# the-bicho.net
KiCad netlist of a schematic drawn in Altium Designer
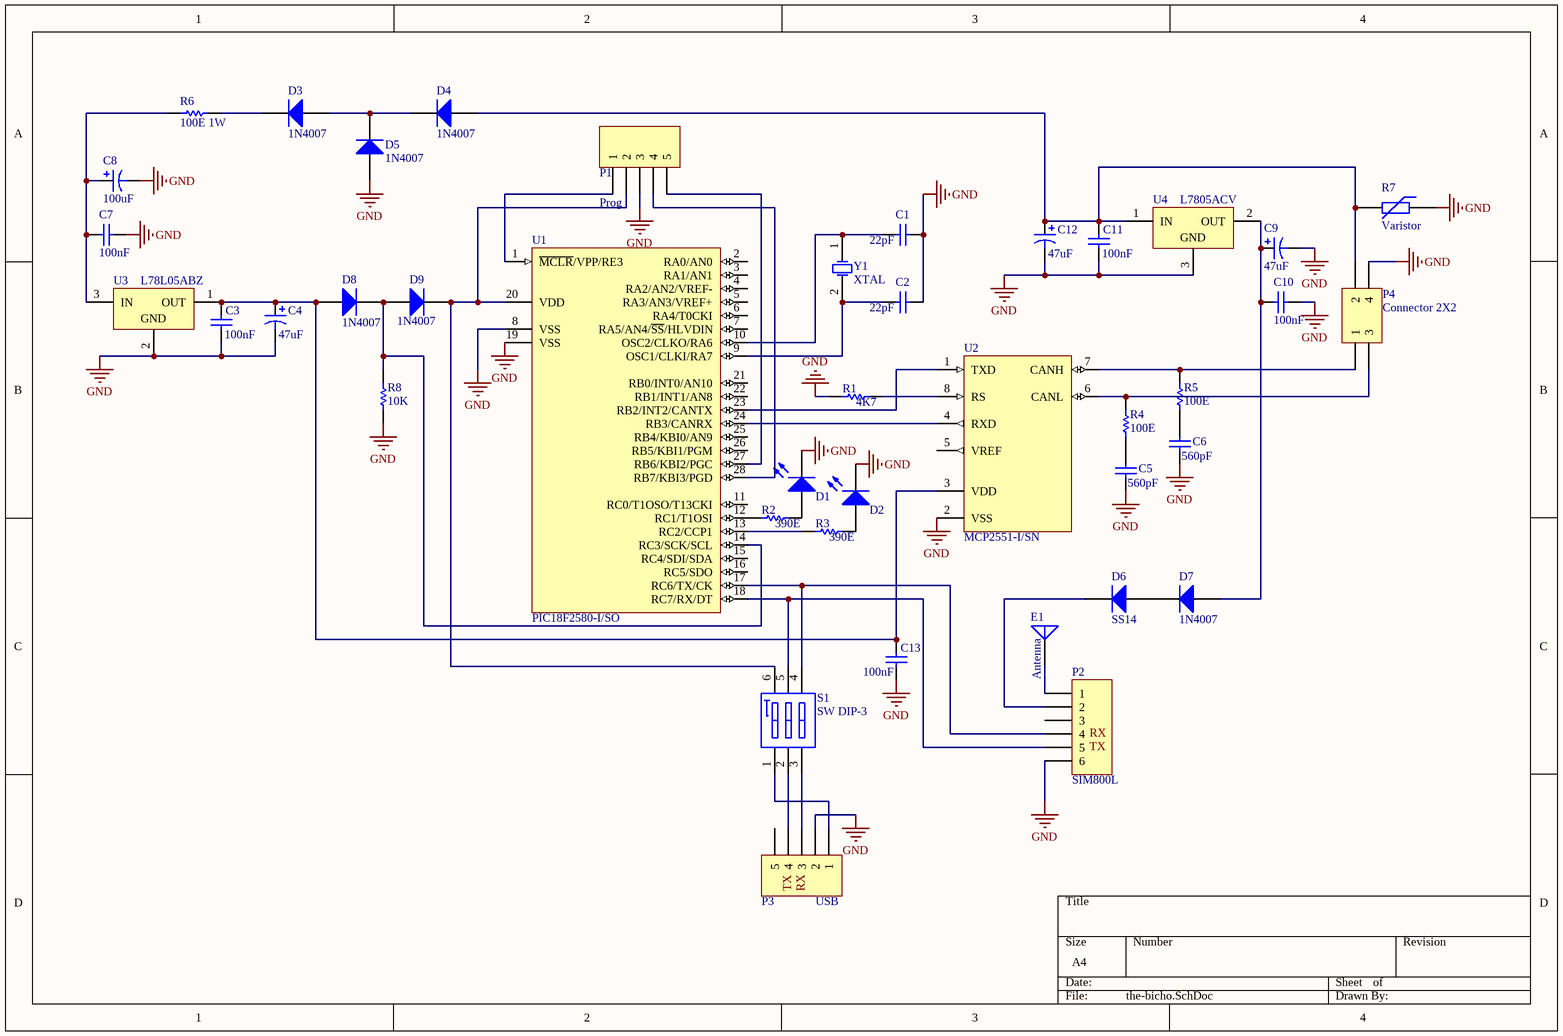
[diagram p0: the-bicho.SchDoc]

(export (version "E")
  (design (tool "Eeschema 10.0.6"))
  (components
    (comp (ref "C1")
      (value "22pF")
      (footprint "C0805:PCBComponent_1")
      (description "Capacitor")
      (fields (field (name "PUBLISHER") "Altium Limited"))
      (libsource (lib "Miscellaneous Devices") (part "Cap"))
    )
    (comp (ref "C2")
      (value "22pF")
      (footprint "C0805:PCBComponent_1")
      (description "Capacitor")
      (fields (field (name "PUBLISHER") "Altium Limited"))
      (libsource (lib "Miscellaneous Devices") (part "Cap"))
    )
    (comp (ref "C3")
      (value "100nF")
      (footprint "C0805:PCBComponent_1")
      (description "Capacitor")
      (fields (field (name "PUBLISHER") "Altium Limited"))
      (libsource (lib "Miscellaneous Devices") (part "Cap"))
    )
    (comp (ref "C4")
      (value "47uF")
      (footprint "C-electro:PCBComponent_1")
      (description "Polarized Capacitor (Radial)")
      (fields (field (name "PUBLISHER") "Altium Limited"))
      (libsource (lib "Miscellaneous Devices") (part "Cap Pol1"))
    )
    (comp (ref "C5")
      (value "560pF")
      (footprint "C0805:PCBComponent_1")
      (description "Capacitor")
      (fields (field (name "PUBLISHER") "Altium Limited"))
      (libsource (lib "Miscellaneous Devices") (part "Cap"))
    )
    (comp (ref "C6")
      (value "560pF")
      (footprint "C0805:PCBComponent_1")
      (description "Capacitor")
      (fields (field (name "PUBLISHER") "Altium Limited"))
      (libsource (lib "Miscellaneous Devices") (part "Cap"))
    )
    (comp (ref "C7")
      (value "100nF")
      (footprint "C0805:PCBComponent_1")
      (description "Capacitor")
      (fields (field (name "PUBLISHER") "Altium Limited"))
      (libsource (lib "Miscellaneous Devices") (part "Cap"))
    )
    (comp (ref "C8")
      (value "100uF")
      (footprint "C-electro:PCBComponent_1")
      (description "Polarized Capacitor (Radial)")
      (fields (field (name "PUBLISHER") "Altium Limited"))
      (libsource (lib "Miscellaneous Devices") (part "Cap Pol1"))
    )
    (comp (ref "C9")
      (value "47uF")
      (footprint "C-electro:PCBComponent_1")
      (description "Polarized Capacitor (Radial)")
      (fields (field (name "PUBLISHER") "Altium Limited"))
      (libsource (lib "Miscellaneous Devices") (part "Cap Pol1"))
    )
    (comp (ref "C10")
      (value "100nF")
      (footprint "C0805:PCBComponent_1")
      (description "Capacitor")
      (fields (field (name "PUBLISHER") "Altium Limited"))
      (libsource (lib "Miscellaneous Devices") (part "Cap"))
    )
    (comp (ref "C11")
      (value "100nF")
      (footprint "C0805:PCBComponent_1")
      (description "Capacitor")
      (fields (field (name "PUBLISHER") "Altium Limited"))
      (libsource (lib "Miscellaneous Devices") (part "Cap"))
    )
    (comp (ref "C12")
      (value "47uF")
      (footprint "C-electro:PCBComponent_1")
      (description "Polarized Capacitor (Radial)")
      (fields (field (name "PUBLISHER") "Altium Limited"))
      (libsource (lib "Miscellaneous Devices") (part "Cap Pol1"))
    )
    (comp (ref "C13")
      (value "100nF")
      (footprint "C0805:PCBComponent_1")
      (description "Capacitor")
      (fields (field (name "PUBLISHER") "Altium Limited"))
      (libsource (lib "Miscellaneous Devices") (part "Cap"))
    )
    (comp (ref "D1")
      (value "~")
      (footprint "Led smd 90:PCBComponent_1")
      (description "Typical INFRARED GaAs LED")
      (fields (field (name "PUBLISHER") "Altium Limited"))
      (libsource (lib "Miscellaneous Devices") (part "LED0"))
    )
    (comp (ref "D2")
      (value "~")
      (footprint "Led smd 90:PCBComponent_1")
      (description "Typical INFRARED GaAs LED")
      (fields (field (name "PUBLISHER") "Altium Limited"))
      (libsource (lib "Miscellaneous Devices") (part "LED0"))
    )
    (comp (ref "D3")
      (value "1N4007")
      (footprint "Diodo SMD:PCBComponent_1")
      (description "1 Amp General Purpose Rectifier")
      (fields (field (name "PUBLISHER") "Altium Limited"))
      (libsource (lib "Miscellaneous Devices") (part "Diode 1N4007"))
    )
    (comp (ref "D4")
      (value "1N4007")
      (footprint "Diodo SMD:PCBComponent_1")
      (description "1 Amp General Purpose Rectifier")
      (fields (field (name "PUBLISHER") "Altium Limited"))
      (libsource (lib "Miscellaneous Devices") (part "Diode 1N4007"))
    )
    (comp (ref "D5")
      (value "1N4007")
      (footprint "Diodo SMD:PCBComponent_1")
      (description "1 Amp General Purpose Rectifier")
      (fields (field (name "PUBLISHER") "Altium Limited"))
      (libsource (lib "Miscellaneous Devices") (part "Diode 1N4007"))
    )
    (comp (ref "D6")
      (value "SS14")
      (footprint "Diodo SMD:PCBComponent_1")
      (description "1 Amp General Purpose Rectifier")
      (fields (field (name "PUBLISHER") "Altium Limited"))
      (libsource (lib "Miscellaneous Devices") (part "Diode 1N4007"))
    )
    (comp (ref "D7")
      (value "1N4007")
      (footprint "Diodo SMD:PCBComponent_1")
      (description "1 Amp General Purpose Rectifier")
      (fields (field (name "PUBLISHER") "Altium Limited"))
      (libsource (lib "Miscellaneous Devices") (part "Diode 1N4007"))
    )
    (comp (ref "D8")
      (value "1N4007")
      (footprint "Diodo SMD:PCBComponent_1")
      (description "1 Amp General Purpose Rectifier")
      (fields (field (name "PUBLISHER") "Altium Limited"))
      (libsource (lib "Miscellaneous Devices") (part "Diode 1N4007"))
    )
    (comp (ref "D9")
      (value "1N4007")
      (footprint "Diodo SMD:PCBComponent_1")
      (description "1 Amp General Purpose Rectifier")
      (fields (field (name "PUBLISHER") "Altium Limited"))
      (libsource (lib "Miscellaneous Devices") (part "Diode 1N4007"))
    )
    (comp (ref "E1")
      (value "Antenna")
      (footprint "PIN1")
      (description "Generic Antenna")
      (fields (field (name "PUBLISHER") "Altium Limited"))
      (libsource (lib "Miscellaneous Devices") (part "Antenna"))
    )
    (comp (ref "P1")
      (value "Prog")
      (footprint "HDR1X5")
      (description "Header, 5-Pin")
      (fields (field (name "PUBLISHER") "Altium Limited"))
      (libsource (lib "Miscellaneous Connectors") (part "Header 5"))
    )
    (comp (ref "P2")
      (value "SIM800L")
      (footprint "HDR1X6")
      (description "Header, 6-Pin")
      (fields (field (name "PUBLISHER") "Altium Limited"))
      (libsource (lib "Miscellaneous Connectors") (part "Header 6"))
    )
    (comp (ref "P3")
      (value "USB")
      (footprint "HDR1X5")
      (description "Header, 5-Pin")
      (fields (field (name "PUBLISHER") "Altium Limited"))
      (libsource (lib "") (part "Header 5_1"))
    )
    (comp (ref "P4")
      (value "Connector 2X2")
      (footprint "Conec 2x2:PCBComponent_1")
      (description "Header, 2-Pin, Dual row")
      (fields (field (name "PUBLISHER") "Altium Limited"))
      (libsource (lib "Miscellaneous Connectors") (part "Header 2X2"))
    )
    (comp (ref "R1")
      (value "4K7")
      (footprint "R0805:PCBComponent_1")
      (description "Resistor")
      (fields (field (name "PUBLISHER") "Altium Limited"))
      (libsource (lib "Miscellaneous Devices") (part "Res1"))
    )
    (comp (ref "R2")
      (value "390E")
      (footprint "R0805:PCBComponent_1")
      (description "Resistor")
      (fields (field (name "PUBLISHER") "Altium Limited"))
      (libsource (lib "Miscellaneous Devices") (part "Res1"))
    )
    (comp (ref "R3")
      (value "390E")
      (footprint "R0805:PCBComponent_1")
      (description "Resistor")
      (fields (field (name "PUBLISHER") "Altium Limited"))
      (libsource (lib "Miscellaneous Devices") (part "Res1"))
    )
    (comp (ref "R4")
      (value "100E")
      (footprint "R0805:PCBComponent_1")
      (description "Resistor")
      (fields (field (name "PUBLISHER") "Altium Limited"))
      (libsource (lib "Miscellaneous Devices") (part "Res1"))
    )
    (comp (ref "R5")
      (value "100E")
      (footprint "R0805:PCBComponent_1")
      (description "Resistor")
      (fields (field (name "PUBLISHER") "Altium Limited"))
      (libsource (lib "Miscellaneous Devices") (part "Res1"))
    )
    (comp (ref "R6")
      (value "100E 1W")
      (footprint "R1watt:PCBComponent_1")
      (description "Resistor")
      (fields (field (name "PUBLISHER") "Altium Limited"))
      (libsource (lib "Miscellaneous Devices") (part "Res1"))
    )
    (comp (ref "R7")
      (value "Varistor")
      (footprint "Vr-07:PCBComponent_1")
      (description "Varistor (Voltage-Sensitive Resistor)")
      (fields (field (name "PUBLISHER") "Altium Limited"))
      (libsource (lib "Miscellaneous Devices") (part "Res Varistor"))
    )
    (comp (ref "R8")
      (value "10K")
      (footprint "R0805:PCBComponent_1")
      (description "Resistor")
      (fields (field (name "PUBLISHER") "Altium Limited"))
      (libsource (lib "Miscellaneous Devices") (part "Res1"))
    )
    (comp (ref "S1")
      (value "SW DIP-3")
      (footprint "Dip 3 piano:PCBComponent_1")
      (description "DIP Switch, 3 Position, SPST")
      (fields (field (name "PUBLISHER") "Altium Limited"))
      (libsource (lib "Miscellaneous Devices") (part "SW DIP-3"))
    )
    (comp (ref "U1")
      (value "PIC18F2580-I/SO")
      (footprint "SOIC-SO28_N")
      (fields (field (name "PUBLISHER") "Altium Limited"))
      (libsource (lib "Microchip Microcontroller 8-Bit PIC18") (part "PIC18F2580-I/SO"))
    )
    (comp (ref "U2")
      (value "MCP2551-I/SN")
      (footprint "SOIC-SN8_N")
      (description "High-Speed CAN Transceiver, 8-Pin SOIC, Industrial Temperature")
      (fields (field (name "PUBLISHER") "Altium Limited"))
      (libsource (lib "Microchip Interface") (part "MCP2551-I/SN"))
    )
    (comp (ref "U3")
      (value "L78L05ABZ")
      (footprint "78Lxx:PCBComponent_1")
      (description "Positive Voltage Regulator")
      (fields (field (name "PUBLISHER") "Altium Limited"))
      (libsource (lib "ST Power Mgt Voltage Regulator") (part "L78L05ABZ"))
    )
    (comp (ref "U4")
      (value "L7805ACV")
      (footprint "TO220ABN")
      (description "Precision 1A Regulator")
      (fields (field (name "PUBLISHER") "Altium Limited"))
      (libsource (lib "ST Power Mgt Voltage Regulator") (part "L7805ACV"))
    )
    (comp (ref "Y1")
      (value "XTAL")
      (footprint "cristal:PCBComponent_1")
      (description "Crystal Oscillator")
      (fields (field (name "PUBLISHER") "Altium Limited"))
      (libsource (lib "Miscellaneous Devices") (part "XTAL"))
    )
  )
  (nets
    (net (code "3") (name "GND") (class "Default")
      (node (ref "C1") (pin "2") (pinfunction "2_2") (pintype "passive"))
      (node (ref "C10") (pin "1") (pinfunction "1_1") (pintype "passive"))
      (node (ref "C11") (pin "1") (pinfunction "1_1") (pintype "passive"))
      (node (ref "C12") (pin "2") (pinfunction "2_2") (pintype "passive"))
      (node (ref "C13") (pin "1") (pinfunction "1_1") (pintype "passive"))
      (node (ref "C2") (pin "2") (pinfunction "2_2") (pintype "passive"))
      (node (ref "C3") (pin "1") (pinfunction "1_1") (pintype "passive"))
      (node (ref "C4") (pin "2") (pinfunction "2_2") (pintype "passive"))
      (node (ref "C5") (pin "1") (pinfunction "1_1") (pintype "passive"))
      (node (ref "C6") (pin "1") (pinfunction "1_1") (pintype "passive"))
      (node (ref "C7") (pin "1") (pinfunction "1_1") (pintype "passive"))
      (node (ref "C8") (pin "2") (pinfunction "2_2") (pintype "passive"))
      (node (ref "C9") (pin "2") (pinfunction "2_2") (pintype "passive"))
      (node (ref "D1") (pin "2") (pinfunction "K_2") (pintype "passive"))
      (node (ref "D2") (pin "2") (pinfunction "K_2") (pintype "passive"))
      (node (ref "D5") (pin "1") (pinfunction "A_1") (pintype "passive"))
      (node (ref "P1") (pin "3") (pinfunction "3_3") (pintype "passive"))
      (node (ref "P2") (pin "6") (pinfunction "6_6") (pintype "passive"))
      (node (ref "P3") (pin "2") (pinfunction "2_2") (pintype "passive"))
      (node (ref "P4") (pin "4") (pinfunction "4_4") (pintype "passive"))
      (node (ref "R1") (pin "1") (pinfunction "1_1") (pintype "passive"))
      (node (ref "R7") (pin "1") (pinfunction "1_1") (pintype "passive"))
      (node (ref "R8") (pin "1") (pinfunction "1_1") (pintype "passive"))
      (node (ref "U1") (pin "19") (pinfunction "VSS_19") (pintype "power_in"))
      (node (ref "U1") (pin "8") (pinfunction "VSS_8") (pintype "power_in"))
      (node (ref "U2") (pin "2") (pinfunction "VSS_2") (pintype "power_in"))
      (node (ref "U3") (pin "2") (pinfunction "GND_2") (pintype "power_in"))
      (node (ref "U4") (pin "3") (pinfunction "GND_3") (pintype "power_in"))
    )
    (net (code "4") (name "Net-(C5-Pad2)") (class "Default")
      (node (ref "C5") (pin "2") (pinfunction "2_2") (pintype "passive"))
      (node (ref "R4") (pin "1") (pinfunction "1_1") (pintype "passive"))
    )
    (net (code "5") (name "Net-(C6-Pad2)") (class "Default")
      (node (ref "C6") (pin "2") (pinfunction "2_2") (pintype "passive"))
      (node (ref "R5") (pin "1") (pinfunction "1_1") (pintype "passive"))
    )
    (net (code "6") (name "Net-(D1-A)") (class "Default")
      (node (ref "D1") (pin "1") (pinfunction "A_1") (pintype "passive"))
      (node (ref "R2") (pin "2") (pinfunction "2_2") (pintype "passive"))
    )
    (net (code "7") (name "Net-(D2-A)") (class "Default")
      (node (ref "D2") (pin "1") (pinfunction "A_1") (pintype "passive"))
      (node (ref "R3") (pin "2") (pinfunction "2_2") (pintype "passive"))
    )
    (net (code "8") (name "Net-(D3-A)") (class "Default")
      (node (ref "D3") (pin "1") (pinfunction "A_1") (pintype "passive"))
      (node (ref "D4") (pin "2") (pinfunction "K_2") (pintype "passive"))
      (node (ref "D5") (pin "2") (pinfunction "K_2") (pintype "passive"))
    )
    (net (code "9") (name "Net-(D3-K)") (class "Default")
      (node (ref "D3") (pin "2") (pinfunction "K_2") (pintype "passive"))
      (node (ref "R6") (pin "1") (pinfunction "1_1") (pintype "passive"))
    )
    (net (code "10") (name "Net-(D4-A)") (class "Default")
      (node (ref "C11") (pin "2") (pinfunction "2_2") (pintype "passive"))
      (node (ref "C12") (pin "1") (pinfunction "1_1") (pintype "passive"))
      (node (ref "D4") (pin "1") (pinfunction "A_1") (pintype "passive"))
      (node (ref "P4") (pin "2") (pinfunction "2_2") (pintype "passive"))
      (node (ref "R7") (pin "2") (pinfunction "2_2") (pintype "passive"))
      (node (ref "U4") (pin "1") (pinfunction "IN_1") (pintype "power_in"))
    )
    (net (code "11") (name "Net-(D6-A)") (class "Default")
      (node (ref "D6") (pin "1") (pinfunction "A_1") (pintype "passive"))
      (node (ref "D7") (pin "2") (pinfunction "K_2") (pintype "passive"))
    )
    (net (code "12") (name "Net-(D6-K)") (class "Default")
      (node (ref "D6") (pin "2") (pinfunction "K_2") (pintype "passive"))
      (node (ref "P2") (pin "2") (pinfunction "2_2") (pintype "passive"))
    )
    (net (code "13") (name "Net-(D7-A)") (class "Default")
      (node (ref "C10") (pin "2") (pinfunction "2_2") (pintype "passive"))
      (node (ref "C9") (pin "1") (pinfunction "1_1") (pintype "passive"))
      (node (ref "D7") (pin "1") (pinfunction "A_1") (pintype "passive"))
      (node (ref "U4") (pin "2") (pinfunction "OUT_2") (pintype "power_in"))
    )
    (net (code "14") (name "Net-(D8-A)") (class "Default")
      (node (ref "C13") (pin "2") (pinfunction "2_2") (pintype "passive"))
      (node (ref "C3") (pin "2") (pinfunction "2_2") (pintype "passive"))
      (node (ref "C4") (pin "1") (pinfunction "1_1") (pintype "passive"))
      (node (ref "D8") (pin "1") (pinfunction "A_1") (pintype "passive"))
      (node (ref "U2") (pin "3") (pinfunction "VDD_3") (pintype "power_in"))
      (node (ref "U3") (pin "1") (pinfunction "OUT_1") (pintype "power_in"))
    )
    (net (code "15") (name "Net-(D8-K)") (class "Default")
      (node (ref "D8") (pin "2") (pinfunction "K_2") (pintype "passive"))
      (node (ref "D9") (pin "1") (pinfunction "A_1") (pintype "passive"))
      (node (ref "R8") (pin "2") (pinfunction "2_2") (pintype "passive"))
      (node (ref "U1") (pin "14") (pinfunction "RC3/SCK/SCL_14") (pintype "bidirectional"))
    )
    (net (code "16") (name "Net-(D9-K)") (class "Default")
      (node (ref "D9") (pin "2") (pinfunction "K_2") (pintype "passive"))
      (node (ref "P1") (pin "2") (pinfunction "2_2") (pintype "passive"))
      (node (ref "S1") (pin "6") (pinfunction "B1_6") (pintype "passive"))
      (node (ref "U1") (pin "20") (pinfunction "VDD_20") (pintype "power_in"))
    )
    (net (code "17") (name "Net-(E1-A)") (class "Default")
      (node (ref "E1") (pin "1") (pinfunction "A_1") (pintype "passive"))
      (node (ref "P2") (pin "1") (pinfunction "1_1") (pintype "passive"))
    )
    (net (code "18") (name "Net-(S1-A1)") (class "Default")
      (node (ref "P3") (pin "1") (pinfunction "1_1") (pintype "passive"))
      (node (ref "S1") (pin "1") (pinfunction "A1_1") (pintype "passive"))
    )
    (net (code "19") (name "Net-(S1-A2)") (class "Default")
      (node (ref "P3") (pin "4") (pinfunction "4_4") (pintype "passive"))
      (node (ref "S1") (pin "2") (pinfunction "A2_2") (pintype "passive"))
    )
    (net (code "20") (name "Net-(S1-A3)") (class "Default")
      (node (ref "P3") (pin "3") (pinfunction "3_3") (pintype "passive"))
      (node (ref "S1") (pin "3") (pinfunction "A3_3") (pintype "passive"))
    )
    (net (code "21") (name "Net-(S1-B2)") (class "Default")
      (node (ref "P2") (pin "5") (pinfunction "5_5") (pintype "passive"))
      (node (ref "S1") (pin "5") (pinfunction "B2_5") (pintype "passive"))
      (node (ref "U1") (pin "18") (pinfunction "RC7/RX/DT_18") (pintype "bidirectional"))
    )
    (net (code "22") (name "Net-(S1-B3)") (class "Default")
      (node (ref "P2") (pin "4") (pinfunction "4_4") (pintype "passive"))
      (node (ref "S1") (pin "4") (pinfunction "B3_4") (pintype "passive"))
      (node (ref "U1") (pin "17") (pinfunction "RC6/TX/CK_17") (pintype "bidirectional"))
    )
    (net (code "23") (name "Net-(U1-OSC1{slash}CLKI{slash}RA7)") (class "Default")
      (node (ref "C2") (pin "1") (pinfunction "1_1") (pintype "passive"))
      (node (ref "U1") (pin "9") (pinfunction "OSC1/CLKI/RA7_9") (pintype "bidirectional"))
      (node (ref "Y1") (pin "2") (pinfunction "OSC2_2") (pintype "passive"))
    )
    (net (code "24") (name "Net-(U1-OSC2{slash}CLKO{slash}RA6)") (class "Default")
      (node (ref "C1") (pin "1") (pinfunction "1_1") (pintype "passive"))
      (node (ref "U1") (pin "10") (pinfunction "OSC2/CLKO/RA6_10") (pintype "bidirectional"))
      (node (ref "Y1") (pin "1") (pinfunction "OSC1_1") (pintype "passive"))
    )
    (net (code "25") (name "Net-(U1-RB2{slash}INT2{slash}CANTX)") (class "Default")
      (node (ref "U1") (pin "23") (pinfunction "RB2/INT2/CANTX_23") (pintype "bidirectional"))
      (node (ref "U2") (pin "1") (pinfunction "TXD_1") (pintype "input"))
    )
    (net (code "26") (name "Net-(U1-RB3{slash}CANRX)") (class "Default")
      (node (ref "U1") (pin "24") (pinfunction "RB3/CANRX_24") (pintype "bidirectional"))
      (node (ref "U2") (pin "4") (pinfunction "RXD_4") (pintype "output"))
    )
    (net (code "27") (name "Net-(U1-RB6{slash}KBI2{slash}PGC)") (class "Default")
      (node (ref "P1") (pin "5") (pinfunction "5_5") (pintype "passive"))
      (node (ref "U1") (pin "27") (pinfunction "RB6/KBI2/PGC_27") (pintype "bidirectional"))
    )
    (net (code "28") (name "Net-(U1-RB7{slash}KBI3{slash}PGD)") (class "Default")
      (node (ref "P1") (pin "4") (pinfunction "4_4") (pintype "passive"))
      (node (ref "U1") (pin "28") (pinfunction "RB7/KBI3/PGD_28") (pintype "bidirectional"))
    )
    (net (code "29") (name "Net-(U1-RC1{slash}T1OSI)") (class "Default")
      (node (ref "R2") (pin "1") (pinfunction "1_1") (pintype "passive"))
      (node (ref "U1") (pin "12") (pinfunction "RC1/T1OSI_12") (pintype "bidirectional"))
    )
    (net (code "30") (name "Net-(U1-RC2{slash}CCP1)") (class "Default")
      (node (ref "R3") (pin "1") (pinfunction "1_1") (pintype "passive"))
      (node (ref "U1") (pin "13") (pinfunction "RC2/CCP1_13") (pintype "bidirectional"))
    )
    (net (code "31") (name "Net-(U1-~{MCLR}{slash}VPP{slash}RE3)") (class "Default")
      (node (ref "P1") (pin "1") (pinfunction "1_1") (pintype "passive"))
      (node (ref "U1") (pin "1") (pinfunction "~{MCLR}/VPP/RE3_1") (pintype "input"))
    )
    (net (code "32") (name "Net-(U2-CANH)") (class "Default")
      (node (ref "P4") (pin "1") (pinfunction "1_1") (pintype "passive"))
      (node (ref "R5") (pin "2") (pinfunction "2_2") (pintype "passive"))
      (node (ref "U2") (pin "7") (pinfunction "CANH_7") (pintype "bidirectional"))
    )
    (net (code "33") (name "Net-(U2-CANL)") (class "Default")
      (node (ref "P4") (pin "3") (pinfunction "3_3") (pintype "passive"))
      (node (ref "R4") (pin "2") (pinfunction "2_2") (pintype "passive"))
      (node (ref "U2") (pin "6") (pinfunction "CANL_6") (pintype "bidirectional"))
    )
    (net (code "34") (name "Net-(U2-RS)") (class "Default")
      (node (ref "R1") (pin "2") (pinfunction "2_2") (pintype "passive"))
      (node (ref "U2") (pin "8") (pinfunction "RS_8") (pintype "input"))
    )
    (net (code "35") (name "Net-(U3-IN)") (class "Default")
      (node (ref "C7") (pin "2") (pinfunction "2_2") (pintype "passive"))
      (node (ref "C8") (pin "1") (pinfunction "1_1") (pintype "passive"))
      (node (ref "R6") (pin "2") (pinfunction "2_2") (pintype "passive"))
      (node (ref "U3") (pin "3") (pinfunction "IN_3") (pintype "power_in"))
    )
    (net (code "36") (name "unconnected-(P2-Pad3)") (class "Default")
      (node (ref "P2") (pin "3") (pinfunction "3_3") (pintype "passive"))
    )
    (net (code "37") (name "unconnected-(P3-Pad5)") (class "Default")
      (node (ref "P3") (pin "5") (pinfunction "5_5") (pintype "passive"))
    )
    (net (code "38") (name "unconnected-(U1-RA0{slash}AN0-Pad2)") (class "Default")
      (node (ref "U1") (pin "2") (pinfunction "RA0/AN0_2") (pintype "bidirectional"))
    )
    (net (code "39") (name "unconnected-(U1-RA1{slash}AN1-Pad3)") (class "Default")
      (node (ref "U1") (pin "3") (pinfunction "RA1/AN1_3") (pintype "bidirectional"))
    )
    (net (code "40") (name "unconnected-(U1-RA2{slash}AN2{slash}VREF--Pad4)") (class "Default")
      (node (ref "U1") (pin "4") (pinfunction "RA2/AN2/VREF-_4") (pintype "bidirectional"))
    )
    (net (code "41") (name "unconnected-(U1-RA3{slash}AN3{slash}VREF+-Pad5)") (class "Default")
      (node (ref "U1") (pin "5") (pinfunction "RA3/AN3/VREF+_5") (pintype "bidirectional"))
    )
    (net (code "42") (name "unconnected-(U1-RA4{slash}T0CKI-Pad6)") (class "Default")
      (node (ref "U1") (pin "6") (pinfunction "RA4/T0CKI_6") (pintype "bidirectional"))
    )
    (net (code "43") (name "unconnected-(U1-RA5{slash}AN4{slash}~{SS}{slash}HLVDIN-Pad7)") (class "Default")
      (node (ref "U1") (pin "7") (pinfunction "RA5/AN4/~{SS}/HLVDIN_7") (pintype "bidirectional"))
    )
    (net (code "44") (name "unconnected-(U1-RB0{slash}INT0{slash}AN10-Pad21)") (class "Default")
      (node (ref "U1") (pin "21") (pinfunction "RB0/INT0/AN10_21") (pintype "bidirectional"))
    )
    (net (code "45") (name "unconnected-(U1-RB1{slash}INT1{slash}AN8-Pad22)") (class "Default")
      (node (ref "U1") (pin "22") (pinfunction "RB1/INT1/AN8_22") (pintype "bidirectional"))
    )
    (net (code "46") (name "unconnected-(U1-RB4{slash}KBI0{slash}AN9-Pad25)") (class "Default")
      (node (ref "U1") (pin "25") (pinfunction "RB4/KBI0/AN9_25") (pintype "bidirectional"))
    )
    (net (code "47") (name "unconnected-(U1-RB5{slash}KBI1{slash}PGM-Pad26)") (class "Default")
      (node (ref "U1") (pin "26") (pinfunction "RB5/KBI1/PGM_26") (pintype "bidirectional"))
    )
    (net (code "48") (name "unconnected-(U1-RC0{slash}T1OSO{slash}T13CKI-Pad11)") (class "Default")
      (node (ref "U1") (pin "11") (pinfunction "RC0/T1OSO/T13CKI_11") (pintype "bidirectional"))
    )
    (net (code "49") (name "unconnected-(U1-RC4{slash}SDI{slash}SDA-Pad15)") (class "Default")
      (node (ref "U1") (pin "15") (pinfunction "RC4/SDI/SDA_15") (pintype "bidirectional"))
    )
    (net (code "50") (name "unconnected-(U1-RC5{slash}SDO-Pad16)") (class "Default")
      (node (ref "U1") (pin "16") (pinfunction "RC5/SDO_16") (pintype "bidirectional"))
    )
    (net (code "51") (name "unconnected-(U2-VREF-Pad5)") (class "Default")
      (node (ref "U2") (pin "5") (pinfunction "VREF_5") (pintype "output"))
    )
  )
)
